# sync_rectification_module_smd.net
KiCad netlist of a schematic drawn in Altium Designer
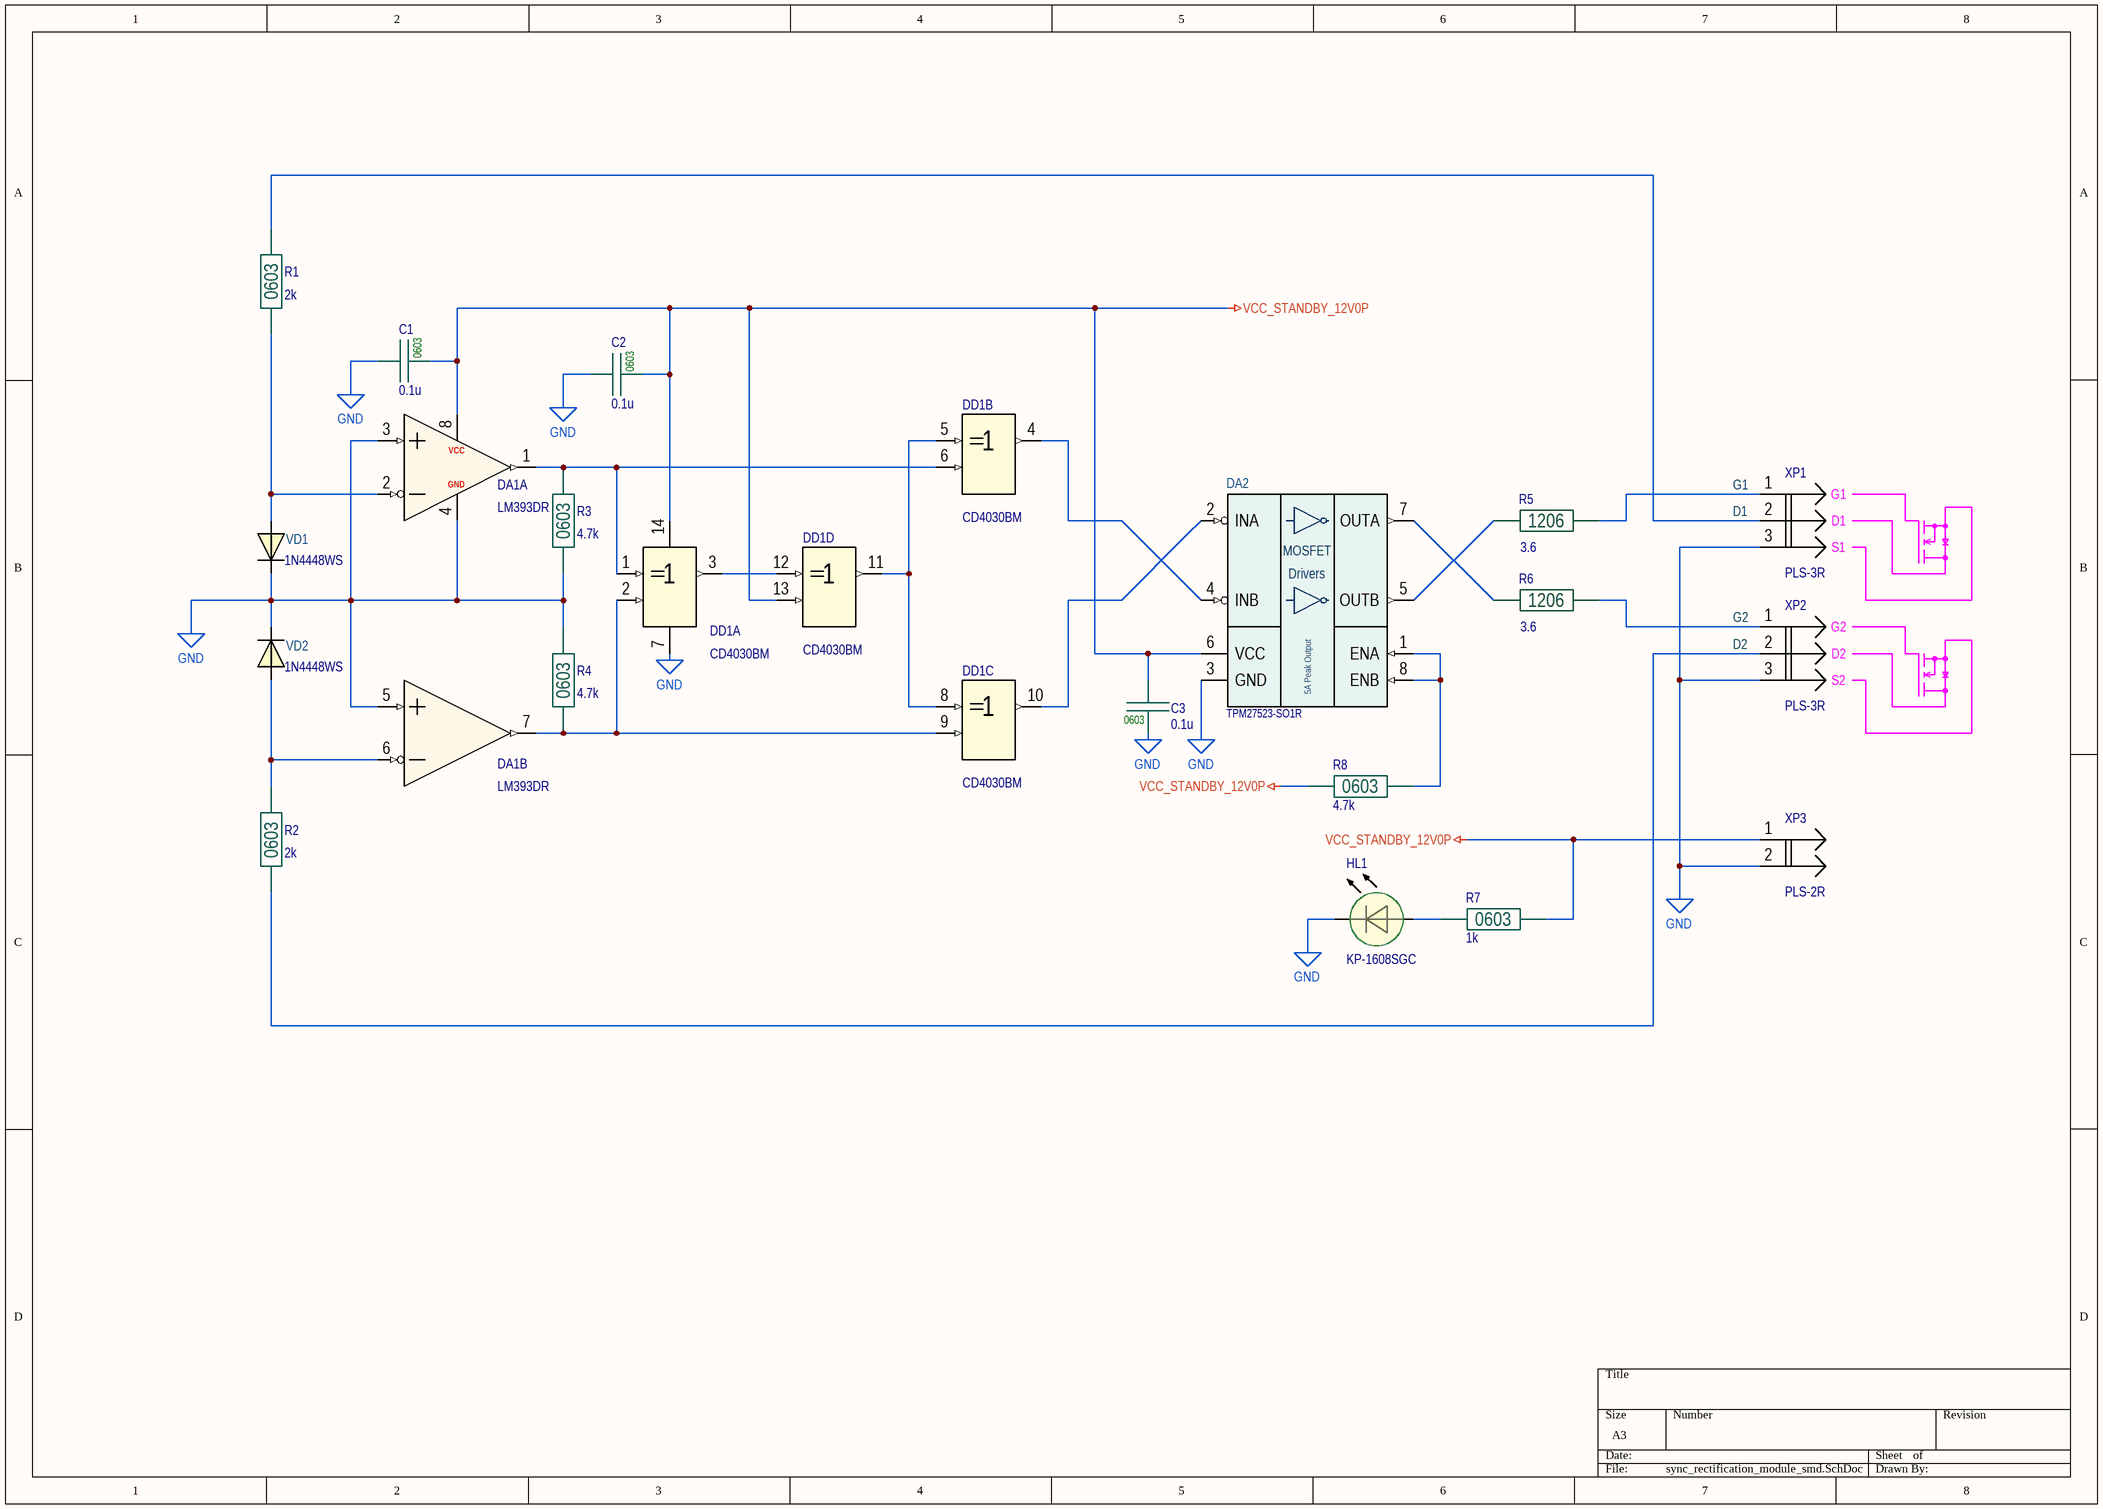
[diagram p0: sync_rectification_module_smd.SchDoc]

(export (version "E")
  (design (tool "Eeschema 10.0.6"))
  (components
    (comp (ref "C1")
      (value "0.1u")
      (footprint "PcbLib_RC:CAP0603")
      (description "Capacitors 0603 package case")
      (fields
        (field (name "TOLERANCE") "± 10 %")
        (field (name "VOLTAGE") "50V")
        (field (name "PACKAGE") "0603")
      )
      (libsource (lib "Schlib_RC") (part "C0603"))
    )
    (comp (ref "C2")
      (value "0.1u")
      (footprint "PcbLib_RC:CAP0603")
      (description "Capacitors 0603 package case")
      (fields
        (field (name "TOLERANCE") "± 10 %")
        (field (name "VOLTAGE") "50V")
        (field (name "PACKAGE") "0603")
      )
      (libsource (lib "Schlib_RC") (part "C0603"))
    )
    (comp (ref "C3")
      (value "0.1u")
      (footprint "PcbLib_RC:CAP0603")
      (description "Capacitors 0603 package case")
      (fields
        (field (name "TOLERANCE") "± 10 %")
        (field (name "VOLTAGE") "50V")
        (field (name "PACKAGE") "0603")
      )
      (libsource (lib "Schlib_RC") (part "C0603"))
    )
    (comp (ref "DA1")
      (value "LM393DR")
      (footprint "PcbLib_ICs:SOIC-8")
      (description "Dual Comparator")
      (fields (field (name "MANUFACTURER") "Texas Instruments"))
      (libsource (lib "Schlib_Texas_Instruments") (part "LM393DR"))
    )
    (comp (ref "DA2")
      (value "TPM27523-SO1R")
      (footprint "PcbLib_ICs:SOIC-8")
      (description "Dual 5-A High-speed, Low-side Gate Driver")
      (fields (field (name "MANUFACTURER") "3PEAK"))
      (libsource (lib "Schlib_3Peak") (part "TPM27523-SO1R"))
    )
    (comp (ref "DD1")
      (value "CD4030BM")
      (footprint "PcbLib_ICs:SOIC-14")
      (description "Quad XOR-Gate")
      (fields (field (name "MANUFACTURER") "Texas Instruments"))
      (libsource (lib "Schlib_Texas_Instruments") (part "CD4030BM"))
    )
    (comp (ref "HL1")
      (value "KP-1608SGC")
      (footprint "PcbLib_Others:LED0603G")
      (description "Super bright green led (package case 0603)")
      (fields (field (name "MANUFACTURER") "Kingbright Company LLC."))
      (libsource (lib "Schlib_Kingbright") (part "KP-1608SGC"))
    )
    (comp (ref "R1")
      (value "2k")
      (footprint "PcbLib_RC:RES0603B")
      (description "Resistor 0603 package case")
      (fields
        (field (name "TOLERANCE") "± 1 %")
        (field (name "PART NUMBER") "RC0603FR-072KL")
        (field (name "PACKAGE") "0603")
      )
      (libsource (lib "Schlib_RC") (part "R0603"))
    )
    (comp (ref "R2")
      (value "2k")
      (footprint "PcbLib_RC:RES0603B")
      (description "Resistor 0603 package case")
      (fields
        (field (name "TOLERANCE") "± 1 %")
        (field (name "PART NUMBER") "RC0603FR-072KL")
        (field (name "PACKAGE") "0603")
      )
      (libsource (lib "Schlib_RC") (part "R0603"))
    )
    (comp (ref "R3")
      (value "4.7k")
      (footprint "PcbLib_RC:RES0603B")
      (description "Resistor 0603 package case")
      (fields
        (field (name "TOLERANCE") "± 1 %")
        (field (name "PART NUMBER") "RC0603FR-074K7L")
        (field (name "PACKAGE") "0603")
      )
      (libsource (lib "Schlib_RC") (part "R0603"))
    )
    (comp (ref "R4")
      (value "4.7k")
      (footprint "PcbLib_RC:RES0603B")
      (description "Resistor 0603 package case")
      (fields
        (field (name "TOLERANCE") "± 1 %")
        (field (name "PART NUMBER") "RC0603FR-074K7L")
        (field (name "PACKAGE") "0603")
      )
      (libsource (lib "Schlib_RC") (part "R0603"))
    )
    (comp (ref "R5")
      (value "3.6")
      (footprint "PcbLib_RC:RES1206B")
      (description "Resistor 1206 package case")
      (fields
        (field (name "TOLERANCE") "± 1 %")
        (field (name "MANUFACTURER") "Yageo")
        (field (name "PACKAGE") "1206")
      )
      (libsource (lib "Schlib_RC") (part "R1206"))
    )
    (comp (ref "R6")
      (value "3.6")
      (footprint "PcbLib_RC:RES1206B")
      (description "Resistor 1206 package case")
      (fields
        (field (name "TOLERANCE") "± 1 %")
        (field (name "MANUFACTURER") "Yageo")
        (field (name "PACKAGE") "1206")
      )
      (libsource (lib "Schlib_RC") (part "R1206"))
    )
    (comp (ref "R7")
      (value "1k")
      (footprint "PcbLib_RC:RES0603B")
      (description "Resistor 0603 package case")
      (fields
        (field (name "TOLERANCE") "± 1 %")
        (field (name "PART NUMBER") "RC0603FR-071KL")
        (field (name "PACKAGE") "0603")
      )
      (libsource (lib "Schlib_RC") (part "R0603"))
    )
    (comp (ref "R8")
      (value "4.7k")
      (footprint "PcbLib_RC:RES0603B")
      (description "Resistor 0603 package case")
      (fields
        (field (name "TOLERANCE") "± 1 %")
        (field (name "PART NUMBER") "RC0603FR-074K7L")
        (field (name "PACKAGE") "0603")
      )
      (libsource (lib "Schlib_RC") (part "R0603"))
    )
    (comp (ref "VD1")
      (value "1N4448WS")
      (footprint "PcbLib_Discrete:SOD-323F")
      (description "Diode 75V, 150mA")
      (fields (field (name "MANUFACTURER") "ON Semiconductor"))
      (libsource (lib "Schlib_ONSemiconductor") (part "1N4448WS"))
    )
    (comp (ref "VD2")
      (value "1N4448WS")
      (footprint "PcbLib_Discrete:SOD-323F")
      (description "Diode 75V, 150mA")
      (fields (field (name "MANUFACTURER") "ON Semiconductor"))
      (libsource (lib "Schlib_ONSemiconductor") (part "1N4448WS"))
    )
    (comp (ref "XP1")
      (value "PLS-3R")
      (footprint "PcbLib_Pin_Headers:PLS-3R")
      (libsource (lib "Schlib_Pin_Headers") (part "PLS-3R"))
    )
    (comp (ref "XP2")
      (value "PLS-3R")
      (footprint "PcbLib_Pin_Headers:PLS-3R")
      (libsource (lib "Schlib_Pin_Headers") (part "PLS-3R"))
    )
    (comp (ref "XP3")
      (value "PLS-2R")
      (footprint "PcbLib_Pin_Headers:PLS-2R")
      (libsource (lib "Schlib_Pin_Headers") (part "PLS-2R"))
    )
  )
  (nets
    (net (code "1") (name "/D1") (class "Default")
      (node (ref "R1") (pin "2") (pinfunction "2_2") (pintype "passive"))
      (node (ref "XP1") (pin "2") (pinfunction "2_2") (pintype "passive"))
    )
    (net (code "2") (name "/D2") (class "Default")
      (node (ref "R2") (pin "1") (pinfunction "1_1") (pintype "passive"))
      (node (ref "XP2") (pin "2") (pinfunction "2_2") (pintype "passive"))
    )
    (net (code "3") (name "/G1") (class "Default")
      (node (ref "R5") (pin "2") (pinfunction "2_2") (pintype "passive"))
      (node (ref "XP1") (pin "1") (pinfunction "1_1") (pintype "passive"))
    )
    (net (code "4") (name "/G2") (class "Default")
      (node (ref "R6") (pin "2") (pinfunction "2_2") (pintype "passive"))
      (node (ref "XP2") (pin "1") (pinfunction "1_1") (pintype "passive"))
    )
    (net (code "5") (name "GND") (class "Default")
      (node (ref "C1") (pin "2") (pinfunction "2_2") (pintype "passive"))
      (node (ref "C2") (pin "2") (pinfunction "2_2") (pintype "passive"))
      (node (ref "C3") (pin "2") (pinfunction "2_2") (pintype "passive"))
      (node (ref "DA1") (pin "3") (pinfunction "1IN+_3") (pintype "input"))
      (node (ref "DA1") (pin "4") (pinfunction "GND_4") (pintype "power_in"))
      (node (ref "DA1") (pin "5") (pinfunction "2IN+_5") (pintype "input"))
      (node (ref "DA2") (pin "3") (pinfunction "GND_3") (pintype "power_in"))
      (node (ref "DD1") (pin "7") (pinfunction "GND_7") (pintype "power_in"))
      (node (ref "HL1") (pin "1") (pinfunction "1_1") (pintype "passive"))
      (node (ref "R3") (pin "1") (pinfunction "1_1") (pintype "passive"))
      (node (ref "R4") (pin "2") (pinfunction "2_2") (pintype "passive"))
      (node (ref "VD1") (pin "1") (pinfunction "C_1") (pintype "passive"))
      (node (ref "VD2") (pin "1") (pinfunction "C_1") (pintype "passive"))
      (node (ref "XP1") (pin "3") (pinfunction "3_3") (pintype "passive"))
      (node (ref "XP2") (pin "3") (pinfunction "3_3") (pintype "passive"))
      (node (ref "XP3") (pin "2") (pinfunction "2_2") (pintype "passive"))
    )
    (net (code "6") (name "Net-(DA1A-1IN-)") (class "Default")
      (node (ref "DA1") (pin "2") (pinfunction "1IN-_2") (pintype "input"))
      (node (ref "R1") (pin "1") (pinfunction "1_1") (pintype "passive"))
      (node (ref "VD1") (pin "2") (pinfunction "A_2") (pintype "passive"))
    )
    (net (code "7") (name "Net-(DA1A-1OUT)") (class "Default")
      (node (ref "DA1") (pin "1") (pinfunction "1OUT_1") (pintype "output"))
      (node (ref "DD1") (pin "1") (pinfunction "A0_1") (pintype "input"))
      (node (ref "DD1") (pin "6") (pinfunction "B1_6") (pintype "input"))
      (node (ref "R3") (pin "2") (pinfunction "2_2") (pintype "passive"))
    )
    (net (code "8") (name "Net-(DA1B-2IN-)") (class "Default")
      (node (ref "DA1") (pin "6") (pinfunction "2IN-_6") (pintype "input"))
      (node (ref "R2") (pin "2") (pinfunction "2_2") (pintype "passive"))
      (node (ref "VD2") (pin "2") (pinfunction "A_2") (pintype "passive"))
    )
    (net (code "9") (name "Net-(DA1B-2OUT)") (class "Default")
      (node (ref "DA1") (pin "7") (pinfunction "2OUT_7") (pintype "output"))
      (node (ref "DD1") (pin "2") (pinfunction "B0_2") (pintype "input"))
      (node (ref "DD1") (pin "9") (pinfunction "B2_9") (pintype "input"))
      (node (ref "R4") (pin "1") (pinfunction "1_1") (pintype "passive"))
    )
    (net (code "10") (name "Net-(DA2-ENA)") (class "Default")
      (node (ref "DA2") (pin "1") (pinfunction "ENA_1") (pintype "input"))
      (node (ref "DA2") (pin "8") (pinfunction "ENB_8") (pintype "input"))
      (node (ref "R8") (pin "1") (pinfunction "1_1") (pintype "passive"))
    )
    (net (code "11") (name "Net-(DA2-INA)") (class "Default")
      (node (ref "DA2") (pin "2") (pinfunction "INA_2") (pintype "input"))
      (node (ref "DD1") (pin "10") (pinfunction "Y2_10") (pintype "output"))
    )
    (net (code "12") (name "Net-(DA2-INB)") (class "Default")
      (node (ref "DA2") (pin "4") (pinfunction "INB_4") (pintype "input"))
      (node (ref "DD1") (pin "4") (pinfunction "Y1_4") (pintype "output"))
    )
    (net (code "13") (name "Net-(DA2-OUTA)") (class "Default")
      (node (ref "DA2") (pin "7") (pinfunction "OUTA_7") (pintype "output"))
      (node (ref "R6") (pin "1") (pinfunction "1_1") (pintype "passive"))
    )
    (net (code "14") (name "Net-(DA2-OUTB)") (class "Default")
      (node (ref "DA2") (pin "5") (pinfunction "OUTB_5") (pintype "output"))
      (node (ref "R5") (pin "1") (pinfunction "1_1") (pintype "passive"))
    )
    (net (code "15") (name "Net-(DD1A-Y0)") (class "Default")
      (node (ref "DD1") (pin "12") (pinfunction "A3_12") (pintype "input"))
      (node (ref "DD1") (pin "3") (pinfunction "Y0_3") (pintype "output"))
    )
    (net (code "16") (name "Net-(DD1B-A1)") (class "Default")
      (node (ref "DD1") (pin "11") (pinfunction "Y3_11") (pintype "output"))
      (node (ref "DD1") (pin "5") (pinfunction "A1_5") (pintype "input"))
      (node (ref "DD1") (pin "8") (pinfunction "A2_8") (pintype "input"))
    )
    (net (code "17") (name "Net-(HL1-Pad2)") (class "Default")
      (node (ref "HL1") (pin "2") (pinfunction "2_2") (pintype "passive"))
      (node (ref "R7") (pin "2") (pinfunction "2_2") (pintype "passive"))
    )
    (net (code "18") (name "VCC_STANDBY_12V0P") (class "Default")
      (node (ref "C1") (pin "1") (pinfunction "1_1") (pintype "passive"))
      (node (ref "C2") (pin "1") (pinfunction "1_1") (pintype "passive"))
      (node (ref "C3") (pin "1") (pinfunction "1_1") (pintype "passive"))
      (node (ref "DA1") (pin "8") (pinfunction "VCC_8") (pintype "power_in"))
      (node (ref "DA2") (pin "6") (pinfunction "VCC_6") (pintype "power_in"))
      (node (ref "DD1") (pin "13") (pinfunction "B3_13") (pintype "input"))
      (node (ref "DD1") (pin "14") (pinfunction "VCC_14") (pintype "power_in"))
      (node (ref "R7") (pin "1") (pinfunction "1_1") (pintype "passive"))
      (node (ref "R8") (pin "2") (pinfunction "2_2") (pintype "passive"))
      (node (ref "XP3") (pin "1") (pinfunction "1_1") (pintype "passive"))
    )
  )
)
